# battery_monitor.net
KiCad netlist of a schematic drawn in EAGLE
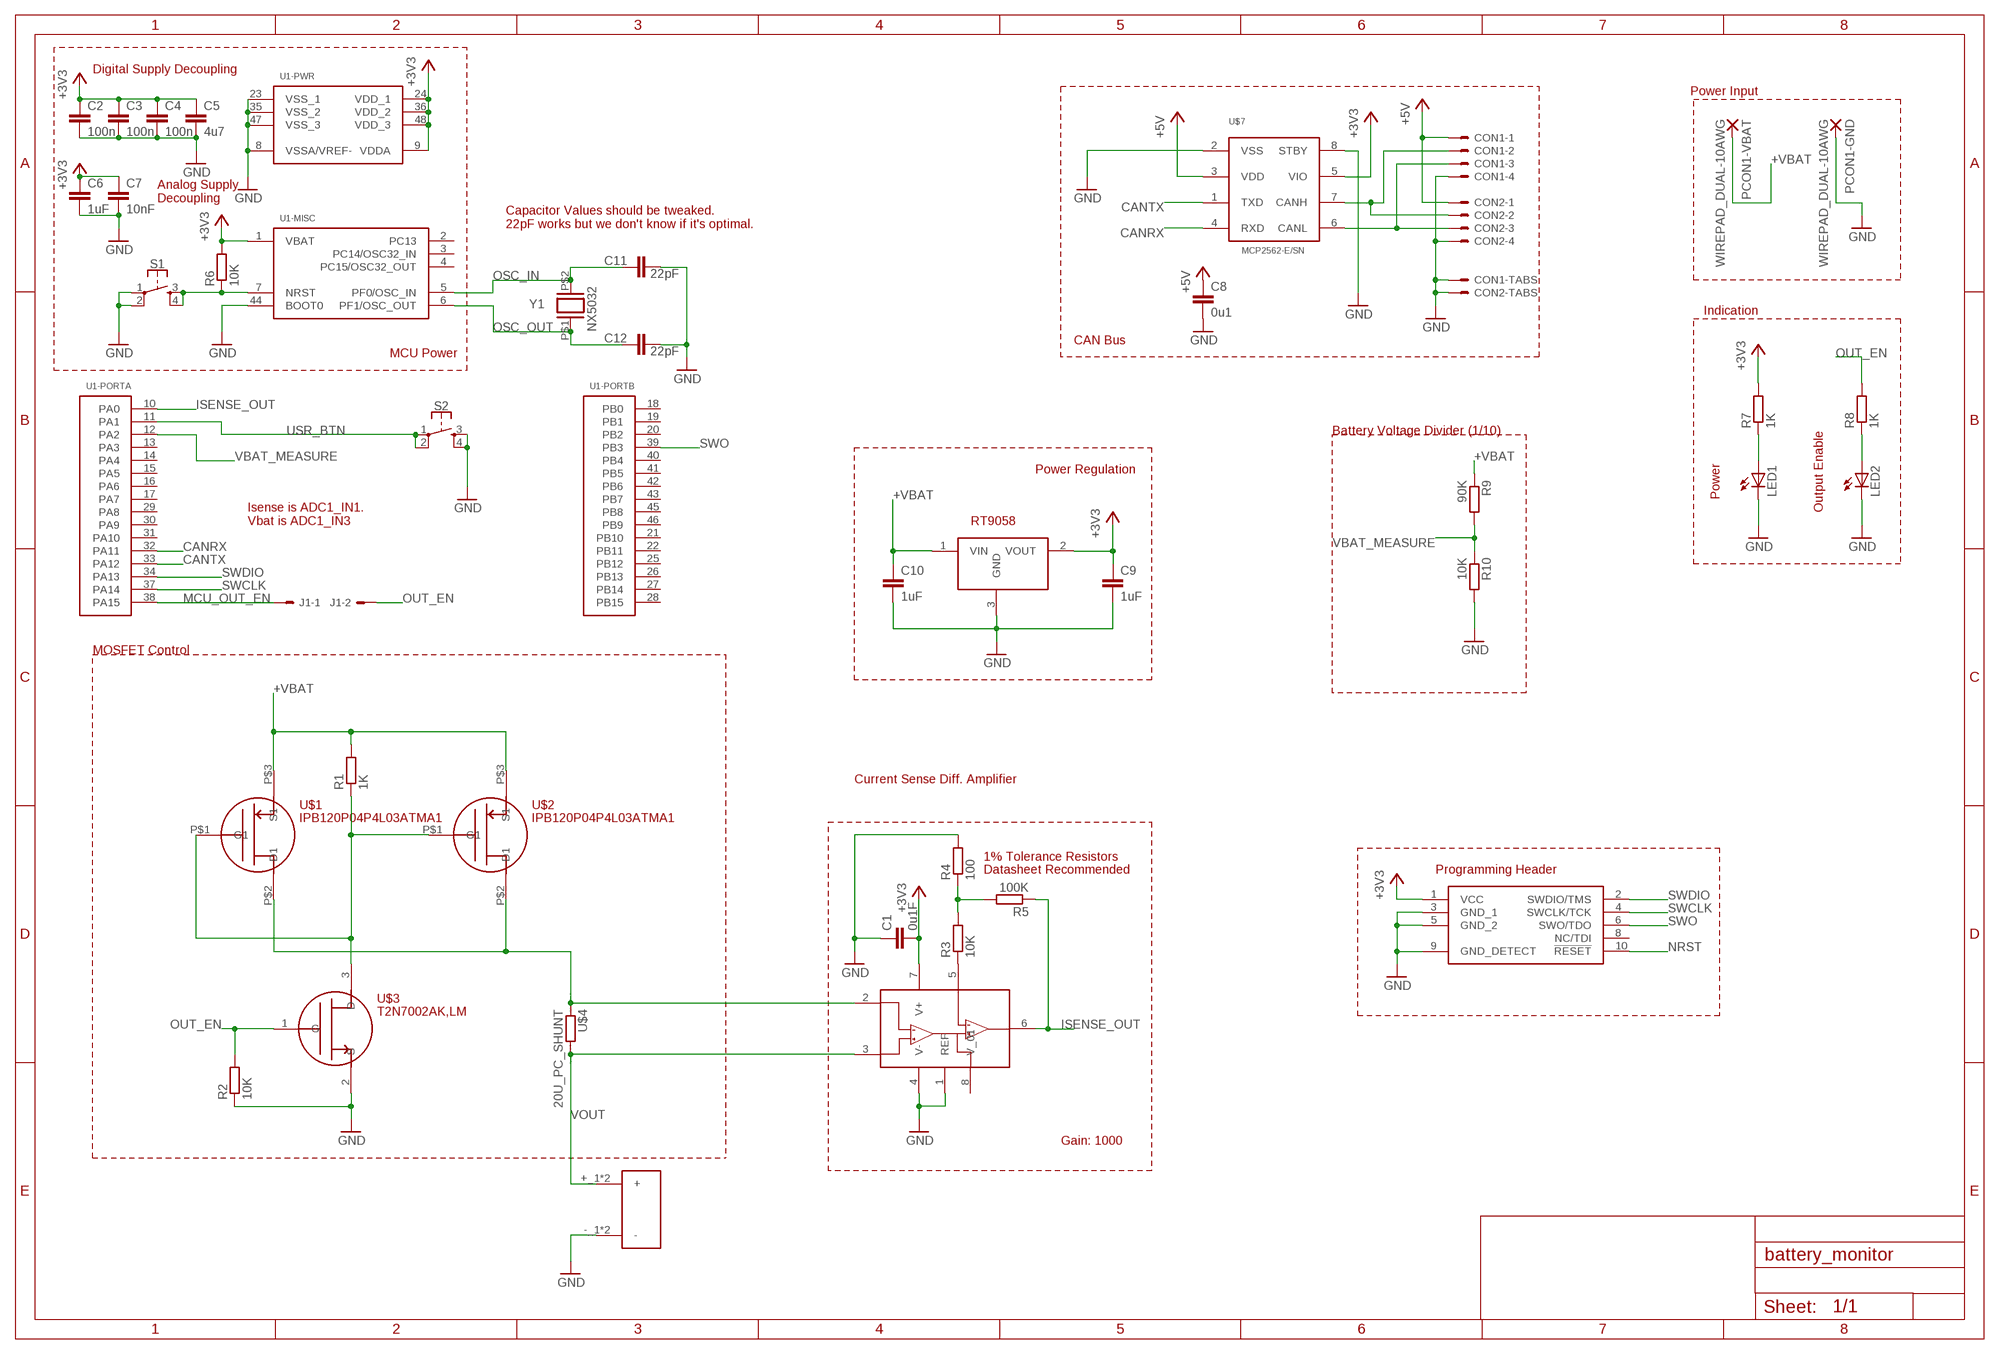
[diagram p0: schematic, sheet 1]

(export (version "E")
  (design (tool "Eeschema 10.0.6"))
  (components
    (comp (ref "C1")
      (value "0u1F")
      (footprint "eagle-import:C0805")
      (libsource (lib "eagle-import") (part "resistor_348_C-EUC0805"))
    )
    (comp (ref "C2")
      (value "100n")
      (footprint "eagle-import:C0805")
      (libsource (lib "eagle-import") (part "resistor_348_C-EUC0805"))
    )
    (comp (ref "C3")
      (value "100n")
      (footprint "eagle-import:C0805")
      (libsource (lib "eagle-import") (part "resistor_348_C-EUC0805"))
    )
    (comp (ref "C4")
      (value "100n")
      (footprint "eagle-import:C0805")
      (libsource (lib "eagle-import") (part "resistor_348_C-EUC0805"))
    )
    (comp (ref "C5")
      (value "4u7")
      (footprint "eagle-import:C0805")
      (libsource (lib "eagle-import") (part "resistor_348_C-EUC0805"))
    )
    (comp (ref "C6")
      (value "1uF")
      (footprint "eagle-import:C0805")
      (libsource (lib "eagle-import") (part "resistor_348_C-EUC0805"))
    )
    (comp (ref "C7")
      (value "10nF")
      (footprint "eagle-import:C0805")
      (libsource (lib "eagle-import") (part "resistor_348_C-EUC0805"))
    )
    (comp (ref "C8")
      (value "0u1")
      (footprint "eagle-import:C0805")
      (libsource (lib "eagle-import") (part "resistor_348_C-EUC0805"))
    )
    (comp (ref "C9")
      (value "1uF")
      (footprint "eagle-import:C0805")
      (libsource (lib "eagle-import") (part "C-EUC0805"))
    )
    (comp (ref "C10")
      (value "1uF")
      (footprint "eagle-import:C0805")
      (libsource (lib "eagle-import") (part "C-EUC0805"))
    )
    (comp (ref "C11")
      (value "22pF")
      (footprint "eagle-import:C0805")
      (libsource (lib "eagle-import") (part "resistor_348_C-EUC0805"))
    )
    (comp (ref "C12")
      (value "22pF")
      (footprint "eagle-import:C0805")
      (libsource (lib "eagle-import") (part "resistor_348_C-EUC0805"))
    )
    (comp (ref "CON1")
      (value "SM04B-GHS-TB")
      (footprint "eagle-import:SM04B-GHS-TB")
      (libsource (lib "eagle-import") (part "SM04B-GHS-TB"))
    )
    (comp (ref "CON2")
      (value "SM04B-GHS-TB")
      (footprint "eagle-import:SM04B-GHS-TB")
      (libsource (lib "eagle-import") (part "SM04B-GHS-TB"))
    )
    (comp (ref "J1")
      (value "2PIN_HDR")
      (footprint "eagle-import:2PIN-HDR")
      (libsource (lib "eagle-import") (part "2PIN_HDR"))
    )
    (comp (ref "JP1")
      (value "CORTEX-M-DBG")
      (footprint "eagle-import:FTSH-105-01-F-DV-007")
      (libsource (lib "eagle-import") (part "CORTEX-M-DBG"))
    )
    (comp (ref "LED1")
      (value "LEDCHIPLED_0805")
      (footprint "eagle-import:CHIPLED_0805")
      (libsource (lib "eagle-import") (part "LEDCHIPLED_0805"))
    )
    (comp (ref "LED2")
      (value "LEDCHIPLED_0805")
      (footprint "eagle-import:CHIPLED_0805")
      (libsource (lib "eagle-import") (part "LEDCHIPLED_0805"))
    )
    (comp (ref "PCON1")
      (value "WIREPAD_DUAL-10AWG")
      (footprint "eagle-import:WIREPAD_DUAL-10AWG")
      (libsource (lib "eagle-import") (part "WIREPAD_DUAL-10AWG"))
    )
    (comp (ref "R1")
      (value "1K")
      (footprint "eagle-import:R0805")
      (libsource (lib "eagle-import") (part "R-EU_R0805"))
    )
    (comp (ref "R2")
      (value "10K")
      (footprint "eagle-import:R0805")
      (libsource (lib "eagle-import") (part "R-EU_R0805"))
    )
    (comp (ref "R3")
      (value "10K")
      (footprint "eagle-import:R0805")
      (libsource (lib "eagle-import") (part "R-EU_R0805"))
    )
    (comp (ref "R4")
      (value "100")
      (footprint "eagle-import:R0805")
      (libsource (lib "eagle-import") (part "R-EU_R0805"))
    )
    (comp (ref "R5")
      (value "100K")
      (footprint "eagle-import:R0805")
      (libsource (lib "eagle-import") (part "R-EU_R0805"))
    )
    (comp (ref "R6")
      (value "10K")
      (footprint "eagle-import:R0805")
      (libsource (lib "eagle-import") (part "R-EU_R0805"))
    )
    (comp (ref "R7")
      (value "1K")
      (footprint "eagle-import:R0805")
      (libsource (lib "eagle-import") (part "R-EU_R0805"))
    )
    (comp (ref "R8")
      (value "1K")
      (footprint "eagle-import:R0805")
      (libsource (lib "eagle-import") (part "R-EU_R0805"))
    )
    (comp (ref "R9")
      (value "90K")
      (footprint "eagle-import:R0805")
      (libsource (lib "eagle-import") (part "R-EU_R0805"))
    )
    (comp (ref "R10")
      (value "10K")
      (footprint "eagle-import:R0805")
      (libsource (lib "eagle-import") (part "R-EU_R0805"))
    )
    (comp (ref "S1")
      (value "MOMENTARY-SWITCH-SPST-2-SMD-4.6X2.8MM")
      (footprint "eagle-import:TACTILE_SWITCH_SMD_4.6X2.8MM")
      (libsource (lib "eagle-import") (part "MOMENTARY-SWITCH-SPST-2-SMD-4.6X2.8MM"))
    )
    (comp (ref "S2")
      (value "MOMENTARY-SWITCH-SPST-2-SMD-4.6X2.8MM")
      (footprint "eagle-import:TACTILE_SWITCH_SMD_4.6X2.8MM")
      (libsource (lib "eagle-import") (part "MOMENTARY-SWITCH-SPST-2-SMD-4.6X2.8MM"))
    )
    (comp (ref "U$1")
      (value "IPB120P04P4L03ATMA1")
      (footprint "eagle-import:INFINEON_PG-TO263-3-2")
      (libsource (lib "eagle-import") (part "IPB120P04P4L03ATMA1"))
    )
    (comp (ref "U$2")
      (value "IPB120P04P4L03ATMA1")
      (footprint "eagle-import:INFINEON_PG-TO263-3-2")
      (libsource (lib "eagle-import") (part "IPB120P04P4L03ATMA1"))
    )
    (comp (ref "U$3")
      (value "T2N7002AK,LM")
      (footprint "eagle-import:SOT23")
      (libsource (lib "eagle-import") (part "T2N7002AK,LM"))
    )
    (comp (ref "U$4")
      (value "20U_PC_SHUNT")
      (footprint "eagle-import:RSENSE_20U")
      (libsource (lib "eagle-import") (part "20U_PC_SHUNT"))
    )
    (comp (ref "U$5")
      (value "PP45_HOR_4GRD")
      (footprint "eagle-import:PP45_HOR_4GRD")
      (libsource (lib "eagle-import") (part "PP45_HOR_4GRD"))
    )
    (comp (ref "U$6")
      (value "INA145")
      (footprint "eagle-import:SOIC8")
      (libsource (lib "eagle-import") (part "INA145"))
    )
    (comp (ref "U$7")
      (value "MCP2562-E/SN")
      (footprint "eagle-import:SOIC8")
      (libsource (lib "eagle-import") (part "MCP2562-E/SN"))
    )
    (comp (ref "U$8")
      (value "RICHTEK_RT9058")
      (footprint "eagle-import:SOT23")
      (libsource (lib "eagle-import") (part "RICHTEK_RT9058"))
    )
    (comp (ref "U1")
      (value "STM32F303CB")
      (footprint "eagle-import:LQFP48")
      (libsource (lib "eagle-import") (part "STM32F303CB"))
    )
    (comp (ref "Y1")
      (value "NX5032")
      (footprint "eagle-import:NX5032")
      (libsource (lib "eagle-import") (part "NX5032"))
    )
  )
  (nets
    (net (code "1") (name "+3V3") (class "Default")
      (node (ref "C1") (pin "2") (pinfunction "2_2") (pintype "passive"))
      (node (ref "C2") (pin "1") (pinfunction "1_1") (pintype "passive"))
      (node (ref "C3") (pin "1") (pinfunction "1_1") (pintype "passive"))
      (node (ref "C4") (pin "1") (pinfunction "1_1") (pintype "passive"))
      (node (ref "C5") (pin "1") (pinfunction "1_1") (pintype "passive"))
      (node (ref "C6") (pin "1") (pinfunction "1_1") (pintype "passive"))
      (node (ref "C7") (pin "1") (pinfunction "1_1") (pintype "passive"))
      (node (ref "C9") (pin "1") (pinfunction "1_1") (pintype "passive"))
      (node (ref "JP1") (pin "1") (pinfunction "VCC_1") (pintype "bidirectional"))
      (node (ref "R6") (pin "2") (pinfunction "2_2") (pintype "passive"))
      (node (ref "R7") (pin "2") (pinfunction "2_2") (pintype "passive"))
      (node (ref "U$6") (pin "7") (pinfunction "V+_7") (pintype "bidirectional"))
      (node (ref "U$7") (pin "5") (pinfunction "VIO_5") (pintype "bidirectional"))
      (node (ref "U$8") (pin "2") (pinfunction "VOUT_2") (pintype "bidirectional"))
      (node (ref "U1") (pin "1") (pinfunction "VBAT_1") (pintype "bidirectional"))
      (node (ref "U1") (pin "24") (pinfunction "VDD_1_24") (pintype "bidirectional"))
      (node (ref "U1") (pin "36") (pinfunction "VDD_2_36") (pintype "bidirectional"))
      (node (ref "U1") (pin "48") (pinfunction "VDD_3_48") (pintype "bidirectional"))
      (node (ref "U1") (pin "9") (pinfunction "VDDA_9") (pintype "bidirectional"))
    )
    (net (code "2") (name "+5V") (class "Default")
      (node (ref "C8") (pin "1") (pinfunction "1_1") (pintype "passive"))
      (node (ref "CON1") (pin "P$1") (pinfunction "S_P$1") (pintype "passive"))
      (node (ref "CON2") (pin "P$1") (pinfunction "S_P$1") (pintype "passive"))
      (node (ref "U$7") (pin "3") (pinfunction "VDD_3") (pintype "bidirectional"))
    )
    (net (code "3") (name "/+VBAT") (class "Default")
      (node (ref "C10") (pin "1") (pinfunction "1_1") (pintype "passive"))
      (node (ref "PCON1") (pin "+") (pinfunction "P_+") (pintype "passive"))
      (node (ref "R1") (pin "2") (pinfunction "2_2") (pintype "passive"))
      (node (ref "R9") (pin "1") (pinfunction "1_1") (pintype "passive"))
      (node (ref "U$1") (pin "P$3") (pinfunction "S1_P$3") (pintype "bidirectional"))
      (node (ref "U$2") (pin "P$3") (pinfunction "S1_P$3") (pintype "bidirectional"))
      (node (ref "U$8") (pin "1") (pinfunction "VIN_1") (pintype "bidirectional"))
    )
    (net (code "4") (name "/CANRX") (class "Default")
      (node (ref "U$7") (pin "4") (pinfunction "RXD_4") (pintype "bidirectional"))
      (node (ref "U1") (pin "32") (pinfunction "PA11_32") (pintype "bidirectional"))
    )
    (net (code "5") (name "/CANTX") (class "Default")
      (node (ref "U$7") (pin "1") (pinfunction "TXD_1") (pintype "bidirectional"))
      (node (ref "U1") (pin "33") (pinfunction "PA12_33") (pintype "bidirectional"))
    )
    (net (code "6") (name "/ISENSE_OUT") (class "Default")
      (node (ref "R5") (pin "1") (pinfunction "1_1") (pintype "passive"))
      (node (ref "U$6") (pin "6") (pinfunction "OUT_6") (pintype "bidirectional"))
      (node (ref "U1") (pin "10") (pinfunction "PA0_10") (pintype "bidirectional"))
    )
    (net (code "7") (name "/MCU_OUT_EN") (class "Default")
      (node (ref "J1") (pin "P$1") (pinfunction "S_P$1") (pintype "passive"))
      (node (ref "U1") (pin "38") (pinfunction "PA15_38") (pintype "bidirectional"))
    )
    (net (code "8") (name "/NRST") (class "Default")
      (node (ref "JP1") (pin "10") (pinfunction "~{RESET}_10") (pintype "bidirectional"))
      (node (ref "R6") (pin "1") (pinfunction "1_1") (pintype "passive"))
      (node (ref "S1") (pin "3") (pinfunction "3_3") (pintype "passive"))
      (node (ref "S1") (pin "4") (pinfunction "4_4") (pintype "passive"))
      (node (ref "U1") (pin "7") (pinfunction "NRST_7") (pintype "bidirectional"))
    )
    (net (code "9") (name "/OSC_IN") (class "Default")
      (node (ref "C11") (pin "1") (pinfunction "1_1") (pintype "passive"))
      (node (ref "U1") (pin "5") (pinfunction "PF0/OSC_IN_5") (pintype "bidirectional"))
      (node (ref "Y1") (pin "P$2") (pinfunction "2_P$2") (pintype "passive"))
    )
    (net (code "10") (name "/OSC_OUT") (class "Default")
      (node (ref "C12") (pin "1") (pinfunction "1_1") (pintype "passive"))
      (node (ref "U1") (pin "6") (pinfunction "PF1/OSC_OUT_6") (pintype "bidirectional"))
      (node (ref "Y1") (pin "P$1") (pinfunction "1_P$1") (pintype "passive"))
    )
    (net (code "11") (name "/OUT_EN") (class "Default")
      (node (ref "J1") (pin "P$2") (pinfunction "S_P$2") (pintype "passive"))
      (node (ref "R2") (pin "2") (pinfunction "2_2") (pintype "passive"))
      (node (ref "R8") (pin "2") (pinfunction "2_2") (pintype "passive"))
      (node (ref "U$3") (pin "1") (pinfunction "G_1") (pintype "bidirectional"))
    )
    (net (code "12") (name "/SWCLK") (class "Default")
      (node (ref "JP1") (pin "4") (pinfunction "SWCLK/TCK_4") (pintype "bidirectional"))
      (node (ref "U1") (pin "37") (pinfunction "PA14_37") (pintype "bidirectional"))
    )
    (net (code "13") (name "/SWDIO") (class "Default")
      (node (ref "JP1") (pin "2") (pinfunction "SWDIO/TMS_2") (pintype "bidirectional"))
      (node (ref "U1") (pin "34") (pinfunction "PA13_34") (pintype "bidirectional"))
    )
    (net (code "14") (name "/SWO") (class "Default")
      (node (ref "JP1") (pin "6") (pinfunction "SWO/TDO_6") (pintype "bidirectional"))
      (node (ref "U1") (pin "39") (pinfunction "PB3_39") (pintype "bidirectional"))
    )
    (net (code "15") (name "/USR_BTN") (class "Default")
      (node (ref "S2") (pin "1") (pinfunction "1_1") (pintype "passive"))
      (node (ref "S2") (pin "2") (pinfunction "2_2") (pintype "passive"))
      (node (ref "U1") (pin "11") (pinfunction "PA1_11") (pintype "bidirectional"))
    )
    (net (code "16") (name "/VBAT_MEASURE") (class "Default")
      (node (ref "R10") (pin "1") (pinfunction "1_1") (pintype "passive"))
      (node (ref "R9") (pin "2") (pinfunction "2_2") (pintype "passive"))
      (node (ref "U1") (pin "12") (pinfunction "PA2_12") (pintype "bidirectional"))
    )
    (net (code "17") (name "/VOUT") (class "Default")
      (node (ref "U$4") (pin "P$2") (pinfunction "2_P$2") (pintype "passive"))
      (node (ref "U$4") (pin "P$4") (pinfunction "2_P$4") (pintype "passive"))
      (node (ref "U$5") (pin "+_1") (pinfunction "+_+_1") (pintype "bidirectional"))
      (node (ref "U$5") (pin "+_2") (pinfunction "+_+_2") (pintype "bidirectional"))
      (node (ref "U$6") (pin "3") (pinfunction "IN+_3") (pintype "bidirectional"))
    )
    (net (code "18") (name "GND") (class "Default")
      (node (ref "C1") (pin "1") (pinfunction "1_1") (pintype "passive"))
      (node (ref "C10") (pin "2") (pinfunction "2_2") (pintype "passive"))
      (node (ref "C11") (pin "2") (pinfunction "2_2") (pintype "passive"))
      (node (ref "C12") (pin "2") (pinfunction "2_2") (pintype "passive"))
      (node (ref "C2") (pin "2") (pinfunction "2_2") (pintype "passive"))
      (node (ref "C3") (pin "2") (pinfunction "2_2") (pintype "passive"))
      (node (ref "C4") (pin "2") (pinfunction "2_2") (pintype "passive"))
      (node (ref "C5") (pin "2") (pinfunction "2_2") (pintype "passive"))
      (node (ref "C6") (pin "2") (pinfunction "2_2") (pintype "passive"))
      (node (ref "C7") (pin "2") (pinfunction "2_2") (pintype "passive"))
      (node (ref "C8") (pin "2") (pinfunction "2_2") (pintype "passive"))
      (node (ref "C9") (pin "2") (pinfunction "2_2") (pintype "passive"))
      (node (ref "CON1") (pin "P$4") (pinfunction "S_P$4") (pintype "passive"))
      (node (ref "CON1") (pin "P$5") (pinfunction "S_P$5") (pintype "passive"))
      (node (ref "CON1") (pin "P$6") (pinfunction "S_P$6") (pintype "passive"))
      (node (ref "CON2") (pin "P$4") (pinfunction "S_P$4") (pintype "passive"))
      (node (ref "CON2") (pin "P$5") (pinfunction "S_P$5") (pintype "passive"))
      (node (ref "CON2") (pin "P$6") (pinfunction "S_P$6") (pintype "passive"))
      (node (ref "JP1") (pin "3") (pinfunction "GND_1_3") (pintype "bidirectional"))
      (node (ref "JP1") (pin "5") (pinfunction "GND_2_5") (pintype "bidirectional"))
      (node (ref "JP1") (pin "9") (pinfunction "GND_DETECT_9") (pintype "bidirectional"))
      (node (ref "LED1") (pin "C") (pinfunction "C_C") (pintype "passive"))
      (node (ref "LED2") (pin "C") (pinfunction "C_C") (pintype "passive"))
      (node (ref "PCON1") (pin "-") (pinfunction "P_-") (pintype "passive"))
      (node (ref "R10") (pin "2") (pinfunction "2_2") (pintype "passive"))
      (node (ref "R2") (pin "1") (pinfunction "1_1") (pintype "passive"))
      (node (ref "R4") (pin "2") (pinfunction "2_2") (pintype "passive"))
      (node (ref "S1") (pin "1") (pinfunction "1_1") (pintype "passive"))
      (node (ref "S1") (pin "2") (pinfunction "2_2") (pintype "passive"))
      (node (ref "S2") (pin "3") (pinfunction "3_3") (pintype "passive"))
      (node (ref "S2") (pin "4") (pinfunction "4_4") (pintype "passive"))
      (node (ref "U$3") (pin "2") (pinfunction "S_2") (pintype "bidirectional"))
      (node (ref "U$5") (pin "-_1") (pinfunction "-_-_1") (pintype "bidirectional"))
      (node (ref "U$5") (pin "-_2") (pinfunction "-_-_2") (pintype "bidirectional"))
      (node (ref "U$6") (pin "1") (pinfunction "REF_1") (pintype "bidirectional"))
      (node (ref "U$6") (pin "4") (pinfunction "V-_4") (pintype "bidirectional"))
      (node (ref "U$7") (pin "2") (pinfunction "VSS_2") (pintype "bidirectional"))
      (node (ref "U$7") (pin "8") (pinfunction "STBY_8") (pintype "bidirectional"))
      (node (ref "U$8") (pin "3") (pinfunction "GND_3") (pintype "bidirectional"))
      (node (ref "U1") (pin "23") (pinfunction "VSS_1_23") (pintype "bidirectional"))
      (node (ref "U1") (pin "35") (pinfunction "VSS_2_35") (pintype "bidirectional"))
      (node (ref "U1") (pin "44") (pinfunction "BOOT0_44") (pintype "bidirectional"))
      (node (ref "U1") (pin "47") (pinfunction "VSS_3_47") (pintype "bidirectional"))
      (node (ref "U1") (pin "8") (pinfunction "VSSA/VREF-_8") (pintype "bidirectional"))
    )
    (net (code "19") (name "Net-(CON1B-S)") (class "Default")
      (node (ref "CON1") (pin "P$2") (pinfunction "S_P$2") (pintype "passive"))
      (node (ref "CON2") (pin "P$2") (pinfunction "S_P$2") (pintype "passive"))
      (node (ref "U$7") (pin "7") (pinfunction "CANH_7") (pintype "bidirectional"))
    )
    (net (code "20") (name "Net-(CON1C-S)") (class "Default")
      (node (ref "CON1") (pin "P$3") (pinfunction "S_P$3") (pintype "passive"))
      (node (ref "CON2") (pin "P$3") (pinfunction "S_P$3") (pintype "passive"))
      (node (ref "U$7") (pin "6") (pinfunction "CANL_6") (pintype "bidirectional"))
    )
    (net (code "21") (name "Net-(LED1-PadA)") (class "Default")
      (node (ref "LED1") (pin "A") (pinfunction "A_A") (pintype "passive"))
      (node (ref "R7") (pin "1") (pinfunction "1_1") (pintype "passive"))
    )
    (net (code "22") (name "Net-(LED2-PadA)") (class "Default")
      (node (ref "LED2") (pin "A") (pinfunction "A_A") (pintype "passive"))
      (node (ref "R8") (pin "1") (pinfunction "1_1") (pintype "passive"))
    )
    (net (code "23") (name "Net-(R3-Pad2)") (class "Default")
      (node (ref "R3") (pin "2") (pinfunction "2_2") (pintype "passive"))
      (node (ref "R4") (pin "1") (pinfunction "1_1") (pintype "passive"))
      (node (ref "R5") (pin "2") (pinfunction "2_2") (pintype "passive"))
    )
    (net (code "24") (name "Net-(U$1-D1)") (class "Default")
      (node (ref "U$1") (pin "P$2") (pinfunction "D1_P$2") (pintype "bidirectional"))
      (node (ref "U$2") (pin "P$2") (pinfunction "D1_P$2") (pintype "bidirectional"))
      (node (ref "U$4") (pin "P$1") (pinfunction "1_P$1") (pintype "passive"))
      (node (ref "U$4") (pin "P$3") (pinfunction "1_P$3") (pintype "passive"))
      (node (ref "U$6") (pin "2") (pinfunction "IN-_2") (pintype "bidirectional"))
    )
    (net (code "25") (name "Net-(U$1-G1)") (class "Default")
      (node (ref "R1") (pin "1") (pinfunction "1_1") (pintype "passive"))
      (node (ref "U$1") (pin "P$1") (pinfunction "G1_P$1") (pintype "bidirectional"))
      (node (ref "U$2") (pin "P$1") (pinfunction "G1_P$1") (pintype "bidirectional"))
      (node (ref "U$3") (pin "3") (pinfunction "D_3") (pintype "bidirectional"))
    )
    (net (code "26") (name "Net-(U$6-VG)") (class "Default")
      (node (ref "R3") (pin "1") (pinfunction "1_1") (pintype "passive"))
      (node (ref "U$6") (pin "5") (pinfunction "VG_5") (pintype "bidirectional"))
    )
    (net (code "27") (name "unconnected-(JP1-NC{slash}TDI-Pad8)") (class "Default")
      (node (ref "JP1") (pin "8") (pinfunction "NC/TDI_8") (pintype "bidirectional"))
    )
    (net (code "28") (name "unconnected-(U$6-V_01-Pad8)") (class "Default")
      (node (ref "U$6") (pin "8") (pinfunction "V_01_8") (pintype "bidirectional"))
    )
    (net (code "29") (name "unconnected-(U1A-PC13-Pad2)") (class "Default")
      (node (ref "U1") (pin "2") (pinfunction "PC13_2") (pintype "bidirectional"))
    )
    (net (code "30") (name "unconnected-(U1A-PC14{slash}OSC32_IN-Pad3)") (class "Default")
      (node (ref "U1") (pin "3") (pinfunction "PC14/OSC32_IN_3") (pintype "bidirectional"))
    )
    (net (code "31") (name "unconnected-(U1A-PC15{slash}OSC32_OUT-Pad4)") (class "Default")
      (node (ref "U1") (pin "4") (pinfunction "PC15/OSC32_OUT_4") (pintype "bidirectional"))
    )
    (net (code "32") (name "unconnected-(U1B-PA3-Pad13)") (class "Default")
      (node (ref "U1") (pin "13") (pinfunction "PA3_13") (pintype "bidirectional"))
    )
    (net (code "33") (name "unconnected-(U1B-PA4-Pad14)") (class "Default")
      (node (ref "U1") (pin "14") (pinfunction "PA4_14") (pintype "bidirectional"))
    )
    (net (code "34") (name "unconnected-(U1B-PA5-Pad15)") (class "Default")
      (node (ref "U1") (pin "15") (pinfunction "PA5_15") (pintype "bidirectional"))
    )
    (net (code "35") (name "unconnected-(U1B-PA6-Pad16)") (class "Default")
      (node (ref "U1") (pin "16") (pinfunction "PA6_16") (pintype "bidirectional"))
    )
    (net (code "36") (name "unconnected-(U1B-PA7-Pad17)") (class "Default")
      (node (ref "U1") (pin "17") (pinfunction "PA7_17") (pintype "bidirectional"))
    )
    (net (code "37") (name "unconnected-(U1B-PA8-Pad29)") (class "Default")
      (node (ref "U1") (pin "29") (pinfunction "PA8_29") (pintype "bidirectional"))
    )
    (net (code "38") (name "unconnected-(U1B-PA9-Pad30)") (class "Default")
      (node (ref "U1") (pin "30") (pinfunction "PA9_30") (pintype "bidirectional"))
    )
    (net (code "39") (name "unconnected-(U1B-PA10-Pad31)") (class "Default")
      (node (ref "U1") (pin "31") (pinfunction "PA10_31") (pintype "bidirectional"))
    )
    (net (code "40") (name "unconnected-(U1C-PB0-Pad18)") (class "Default")
      (node (ref "U1") (pin "18") (pinfunction "PB0_18") (pintype "bidirectional"))
    )
    (net (code "41") (name "unconnected-(U1C-PB1-Pad19)") (class "Default")
      (node (ref "U1") (pin "19") (pinfunction "PB1_19") (pintype "bidirectional"))
    )
    (net (code "42") (name "unconnected-(U1C-PB2-Pad20)") (class "Default")
      (node (ref "U1") (pin "20") (pinfunction "PB2_20") (pintype "bidirectional"))
    )
    (net (code "43") (name "unconnected-(U1C-PB4-Pad40)") (class "Default")
      (node (ref "U1") (pin "40") (pinfunction "PB4_40") (pintype "bidirectional"))
    )
    (net (code "44") (name "unconnected-(U1C-PB5-Pad41)") (class "Default")
      (node (ref "U1") (pin "41") (pinfunction "PB5_41") (pintype "bidirectional"))
    )
    (net (code "45") (name "unconnected-(U1C-PB6-Pad42)") (class "Default")
      (node (ref "U1") (pin "42") (pinfunction "PB6_42") (pintype "bidirectional"))
    )
    (net (code "46") (name "unconnected-(U1C-PB7-Pad43)") (class "Default")
      (node (ref "U1") (pin "43") (pinfunction "PB7_43") (pintype "bidirectional"))
    )
    (net (code "47") (name "unconnected-(U1C-PB8-Pad45)") (class "Default")
      (node (ref "U1") (pin "45") (pinfunction "PB8_45") (pintype "bidirectional"))
    )
    (net (code "48") (name "unconnected-(U1C-PB9-Pad46)") (class "Default")
      (node (ref "U1") (pin "46") (pinfunction "PB9_46") (pintype "bidirectional"))
    )
    (net (code "49") (name "unconnected-(U1C-PB10-Pad21)") (class "Default")
      (node (ref "U1") (pin "21") (pinfunction "PB10_21") (pintype "bidirectional"))
    )
    (net (code "50") (name "unconnected-(U1C-PB11-Pad22)") (class "Default")
      (node (ref "U1") (pin "22") (pinfunction "PB11_22") (pintype "bidirectional"))
    )
    (net (code "51") (name "unconnected-(U1C-PB12-Pad25)") (class "Default")
      (node (ref "U1") (pin "25") (pinfunction "PB12_25") (pintype "bidirectional"))
    )
    (net (code "52") (name "unconnected-(U1C-PB13-Pad26)") (class "Default")
      (node (ref "U1") (pin "26") (pinfunction "PB13_26") (pintype "bidirectional"))
    )
    (net (code "53") (name "unconnected-(U1C-PB14-Pad27)") (class "Default")
      (node (ref "U1") (pin "27") (pinfunction "PB14_27") (pintype "bidirectional"))
    )
    (net (code "54") (name "unconnected-(U1C-PB15-Pad28)") (class "Default")
      (node (ref "U1") (pin "28") (pinfunction "PB15_28") (pintype "bidirectional"))
    )
  )
)
